# pwr_pos_bipolar.net
KiCad netlist of a schematic drawn in EAGLE
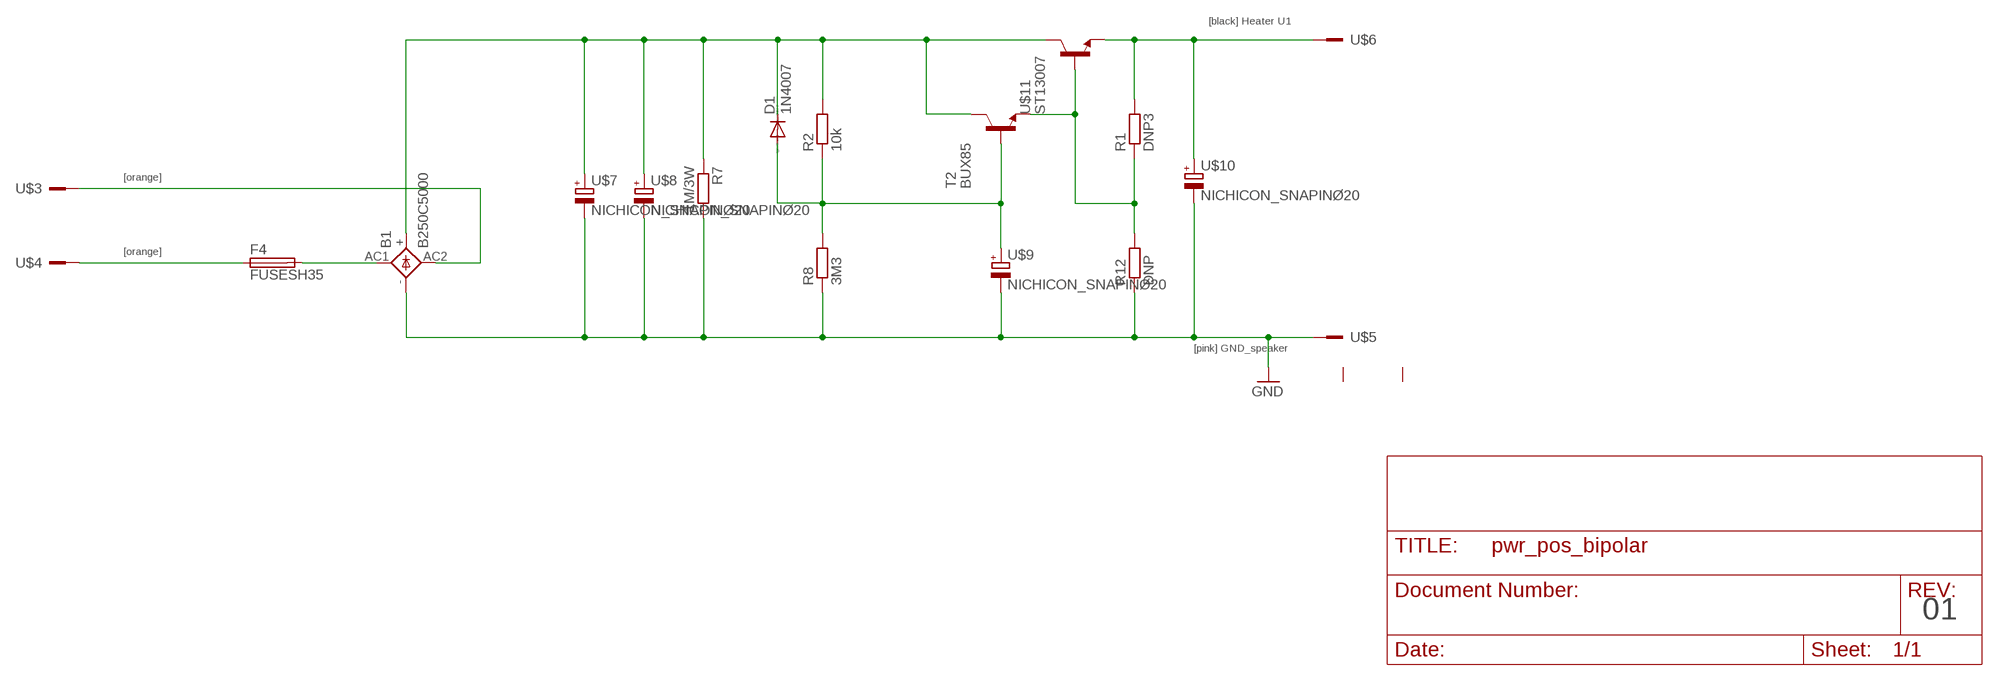
[diagram p0: schematic, sheet 1]

(export (version "E")
  (design (tool "Eeschema 10.0.6"))
  (components
    (comp (ref "B1")
      (value "B250C5000")
      (footprint "eagle-import:DIOTEC_BC5000")
      (libsource (lib "eagle-import") (part "DIOTEC_BC5000"))
    )
    (comp (ref "D1")
      (value "1N4007")
      (footprint "eagle-import:DO41-10")
      (libsource (lib "eagle-import") (part "1N4004"))
    )
    (comp (ref "F4")
      (value "FUSESH35")
      (footprint "eagle-import:SH25")
      (libsource (lib "eagle-import") (part "FUSESH35"))
    )
    (comp (ref "R1")
      (value "DNP3")
      (footprint "eagle-import:0411_12")
      (libsource (lib "eagle-import") (part "R-EU_0411/12"))
    )
    (comp (ref "R2")
      (value "10k")
      (footprint "eagle-import:0411_12")
      (libsource (lib "eagle-import") (part "R-EU_0411/12"))
    )
    (comp (ref "R7")
      (value "1M/3W")
      (footprint "eagle-import:0922V")
      (libsource (lib "eagle-import") (part "R-EU_0922V"))
    )
    (comp (ref "R8")
      (value "3M3")
      (footprint "eagle-import:0411_12")
      (libsource (lib "eagle-import") (part "R-EU_0411/12"))
    )
    (comp (ref "R12")
      (value "DNP")
      (footprint "eagle-import:0411_12")
      (libsource (lib "eagle-import") (part "R-EU_0411/12"))
    )
    (comp (ref "T2")
      (value "BUX85")
      (footprint "eagle-import:TO220V")
      (libsource (lib "eagle-import") (part "-NPN-TO220V"))
    )
    (comp (ref "U$1")
      (value "SK456-60-3XM3L")
      (footprint "eagle-import:SK456-60-3XM3L")
      (libsource (lib "eagle-import") (part "SK456-60-3XM3L"))
    )
    (comp (ref "U$2")
      (value "RN_POWER")
      (footprint "eagle-import:RN")
      (libsource (lib "eagle-import") (part "RN_POWER"))
    )
    (comp (ref "U$3")
      (value "M1")
      (footprint "eagle-import:M1_OFFSET")
      (libsource (lib "eagle-import") (part "M1"))
    )
    (comp (ref "U$4")
      (value "M1")
      (footprint "eagle-import:M1_OFFSET")
      (libsource (lib "eagle-import") (part "M1"))
    )
    (comp (ref "U$5")
      (value "M1")
      (footprint "eagle-import:M1_OFFSET")
      (libsource (lib "eagle-import") (part "M1"))
    )
    (comp (ref "U$6")
      (value "M1")
      (footprint "eagle-import:M1_OFFSET")
      (libsource (lib "eagle-import") (part "M1"))
    )
    (comp (ref "U$7")
      (value "NICHICON_SNAPINØ20")
      (footprint "eagle-import:C_20G10")
      (libsource (lib "eagle-import") (part "NICHICON_SNAPINØ20"))
    )
    (comp (ref "U$8")
      (value "NICHICON_SNAPINØ20")
      (footprint "eagle-import:C_20G10")
      (libsource (lib "eagle-import") (part "NICHICON_SNAPINØ20"))
    )
    (comp (ref "U$9")
      (value "NICHICON_SNAPINØ20")
      (footprint "eagle-import:C_20G10")
      (libsource (lib "eagle-import") (part "NICHICON_SNAPINØ20"))
    )
    (comp (ref "U$10")
      (value "NICHICON_SNAPINØ20")
      (footprint "eagle-import:C_20G10")
      (libsource (lib "eagle-import") (part "NICHICON_SNAPINØ20"))
    )
    (comp (ref "U$11")
      (value "ST13007")
      (footprint "eagle-import:TOP3V_TO220")
      (libsource (lib "eagle-import") (part "NPN-POWER"))
    )
  )
  (nets
    (net (code "1") (name "GND") (class "Default")
      (node (ref "B1") (pin "-") (pinfunction "-_-") (pintype "passive"))
      (node (ref "R12") (pin "1") (pinfunction "1_1") (pintype "passive"))
      (node (ref "R7") (pin "2") (pinfunction "2_2") (pintype "passive"))
      (node (ref "R8") (pin "1") (pinfunction "1_1") (pintype "passive"))
      (node (ref "U$10") (pin "-") (pinfunction "-_-") (pintype "passive"))
      (node (ref "U$5") (pin "1") (pinfunction "KL_1") (pintype "passive"))
      (node (ref "U$7") (pin "-") (pinfunction "-_-") (pintype "passive"))
      (node (ref "U$8") (pin "-") (pinfunction "-_-") (pintype "passive"))
      (node (ref "U$9") (pin "-") (pinfunction "-_-") (pintype "passive"))
    )
    (net (code "2") (name "Net-(B1-PadAC1)") (class "Default")
      (node (ref "B1") (pin "AC1") (pinfunction "AC1_AC1") (pintype "passive"))
      (node (ref "F4") (pin "2") (pinfunction "2_2") (pintype "passive"))
    )
    (net (code "3") (name "Net-(T2-B)") (class "Default")
      (node (ref "D1") (pin "A") (pinfunction "A_A") (pintype "passive"))
      (node (ref "R2") (pin "1") (pinfunction "1_1") (pintype "passive"))
      (node (ref "R8") (pin "2") (pinfunction "2_2") (pintype "passive"))
      (node (ref "T2") (pin "1") (pinfunction "B_1") (pintype "passive"))
      (node (ref "U$9") (pin "+") (pinfunction "+_+") (pintype "passive"))
    )
    (net (code "4") (name "Net-(T2-C)") (class "Default")
      (node (ref "B1") (pin "+") (pinfunction "+_+") (pintype "passive"))
      (node (ref "D1") (pin "C") (pinfunction "C_C") (pintype "passive"))
      (node (ref "R2") (pin "2") (pinfunction "2_2") (pintype "passive"))
      (node (ref "R7") (pin "1") (pinfunction "1_1") (pintype "passive"))
      (node (ref "T2") (pin "2") (pinfunction "C_2") (pintype "passive"))
      (node (ref "U$11") (pin "C") (pinfunction "C_C") (pintype "passive"))
      (node (ref "U$7") (pin "+") (pinfunction "+_+") (pintype "passive"))
      (node (ref "U$8") (pin "+") (pinfunction "+_+") (pintype "passive"))
    )
    (net (code "5") (name "Net-(T2-E)") (class "Default")
      (node (ref "R1") (pin "1") (pinfunction "1_1") (pintype "passive"))
      (node (ref "R12") (pin "2") (pinfunction "2_2") (pintype "passive"))
      (node (ref "T2") (pin "3") (pinfunction "E_3") (pintype "passive"))
      (node (ref "U$11") (pin "B") (pinfunction "B_B") (pintype "passive"))
      (node (ref "U$11") (pin "B$1") (pinfunction "B_B$1") (pintype "passive"))
    )
    (net (code "6") (name "Net-(U$3-KL)") (class "Default")
      (node (ref "B1") (pin "AC2") (pinfunction "AC2_AC2") (pintype "passive"))
      (node (ref "U$3") (pin "1") (pinfunction "KL_1") (pintype "passive"))
    )
    (net (code "7") (name "Net-(U$4-KL)") (class "Default")
      (node (ref "F4") (pin "1") (pinfunction "1_1") (pintype "passive"))
      (node (ref "U$4") (pin "1") (pinfunction "KL_1") (pintype "passive"))
    )
    (net (code "8") (name "Net-(U$6-KL)") (class "Default")
      (node (ref "R1") (pin "2") (pinfunction "2_2") (pintype "passive"))
      (node (ref "U$10") (pin "+") (pinfunction "+_+") (pintype "passive"))
      (node (ref "U$11") (pin "E") (pinfunction "E_E") (pintype "passive"))
      (node (ref "U$11") (pin "E$1") (pinfunction "E_E$1") (pintype "passive"))
      (node (ref "U$6") (pin "1") (pinfunction "KL_1") (pintype "passive"))
    )
    (net (code "9") (name "unconnected-(U$1-PadP$1)") (class "Default")
      (node (ref "U$1") (pin "P$1") (pinfunction "P$1_P$1") (pintype "no_connect"))
    )
    (net (code "10") (name "unconnected-(U$1-PadP$2)") (class "Default")
      (node (ref "U$1") (pin "P$2") (pinfunction "P$2_P$2") (pintype "no_connect"))
    )
    (net (code "11") (name "unconnected-(U$2-P$1-PadSH@1)") (class "Default")
      (node (ref "U$2") (pin "SH@1") (pinfunction "P$1_SH@1") (pintype "no_connect"))
    )
    (net (code "12") (name "unconnected-(U$2-P$2-PadSH@2)") (class "Default")
      (node (ref "U$2") (pin "SH@2") (pinfunction "P$2_SH@2") (pintype "no_connect"))
    )
    (net (code "13") (name "unconnected-(U$2-P$3-PadSH@3)") (class "Default")
      (node (ref "U$2") (pin "SH@3") (pinfunction "P$3_SH@3") (pintype "no_connect"))
    )
    (net (code "14") (name "unconnected-(U$2-P$4-PadSH@4)") (class "Default")
      (node (ref "U$2") (pin "SH@4") (pinfunction "P$4_SH@4") (pintype "no_connect"))
    )
  )
)
